# sfx.net
KiCad netlist of a schematic drawn in EAGLE
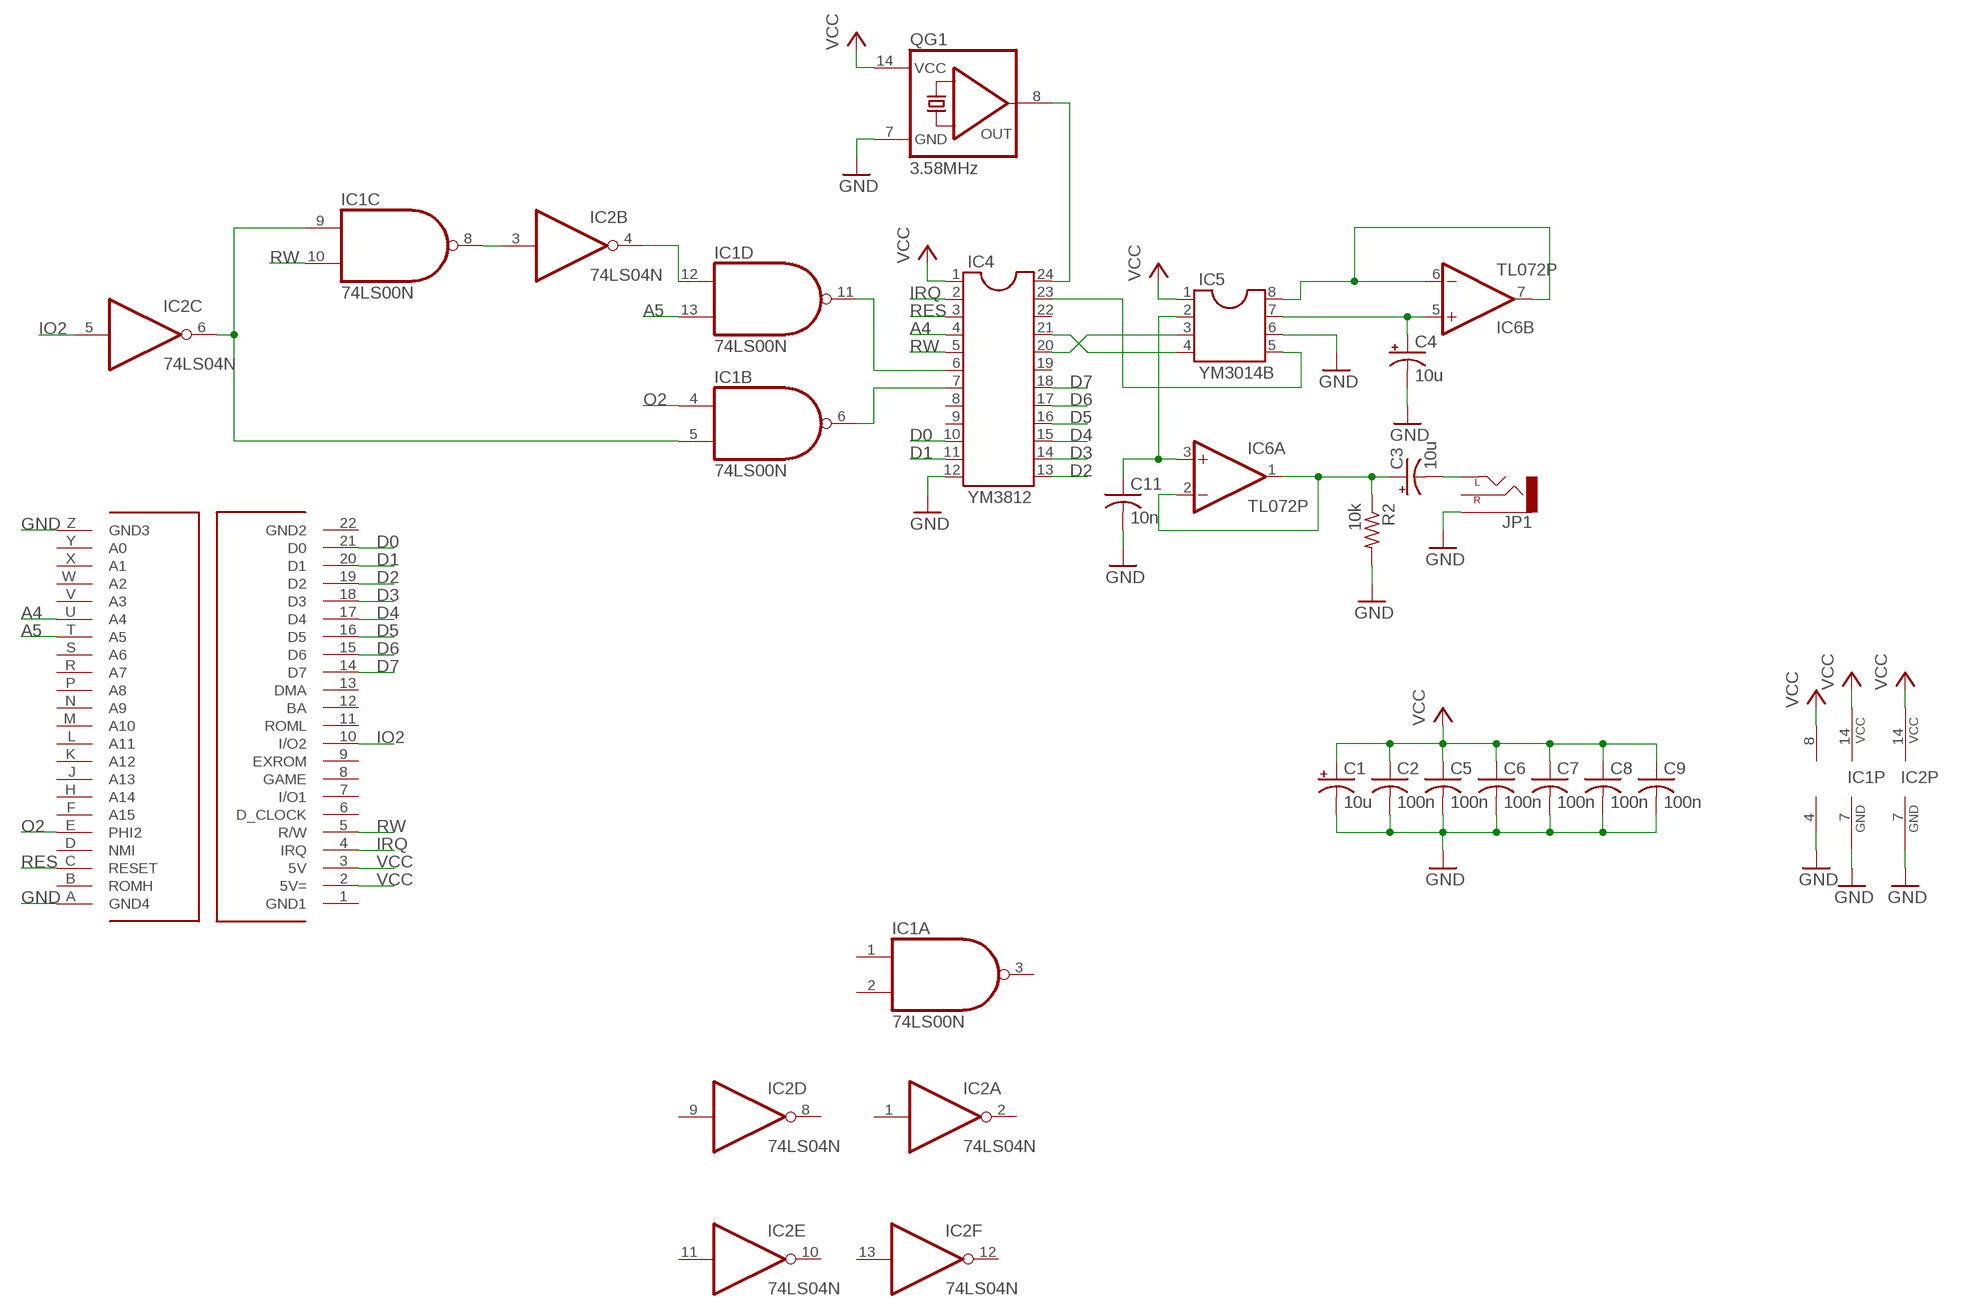
[diagram p0: schematic, sheet 1]

(export (version "E")
  (design (tool "Eeschema 10.0.6"))
  (components
    (comp (ref "C1")
      (value "10u")
      (footprint "eagle-import:E2,5-6")
      (libsource (lib "eagle-import") (part "CPOL-USE2.5-6"))
    )
    (comp (ref "C2")
      (value "100n")
      (footprint "eagle-import:C025-025X050")
      (libsource (lib "eagle-import") (part "C-US025-025X050"))
    )
    (comp (ref "C3")
      (value "10u")
      (footprint "eagle-import:E2,5-6")
      (libsource (lib "eagle-import") (part "CPOL-USE2.5-6"))
    )
    (comp (ref "C4")
      (value "10u")
      (footprint "eagle-import:E2,5-6")
      (libsource (lib "eagle-import") (part "CPOL-USE2.5-6"))
    )
    (comp (ref "C5")
      (value "100n")
      (footprint "eagle-import:C025-025X050")
      (libsource (lib "eagle-import") (part "C-US025-025X050"))
    )
    (comp (ref "C6")
      (value "100n")
      (footprint "eagle-import:C025-025X050")
      (libsource (lib "eagle-import") (part "C-US025-025X050"))
    )
    (comp (ref "C7")
      (value "100n")
      (footprint "eagle-import:C025-025X050")
      (libsource (lib "eagle-import") (part "C-US025-025X050"))
    )
    (comp (ref "C8")
      (value "100n")
      (footprint "eagle-import:C025-025X050")
      (libsource (lib "eagle-import") (part "C-US025-025X050"))
    )
    (comp (ref "C9")
      (value "100n")
      (footprint "eagle-import:C025-025X050")
      (libsource (lib "eagle-import") (part "C-US025-025X050"))
    )
    (comp (ref "C11")
      (value "10n")
      (footprint "eagle-import:C025-025X050")
      (libsource (lib "eagle-import") (part "C-US025-025X050"))
    )
    (comp (ref "IC1")
      (value "74LS00N")
      (footprint "eagle-import:DIL14")
      (libsource (lib "eagle-import") (part "7400NLS"))
    )
    (comp (ref "IC2")
      (value "74LS04N")
      (footprint "eagle-import:DIL14")
      (libsource (lib "eagle-import") (part "7404NLS"))
    )
    (comp (ref "IC4")
      (value "YM3812")
      (footprint "eagle-import:DIL24-6")
      (libsource (lib "eagle-import") (part "DIL24-6"))
    )
    (comp (ref "IC5")
      (value "YM3014B")
      (footprint "eagle-import:DIL08")
      (libsource (lib "eagle-import") (part "DIL8"))
    )
    (comp (ref "IC6")
      (value "TL072P")
      (footprint "eagle-import:DIL08")
      (libsource (lib "eagle-import") (part "TL072P"))
    )
    (comp (ref "JP1")
      (value "AUDIO-JACKPTH")
      (footprint "eagle-import:AUDIO-JACK")
      (libsource (lib "eagle-import") (part "AUDIO-JACKPTH"))
    )
    (comp (ref "QG1")
      (value "3.58MHz")
      (footprint "eagle-import:DIL14S")
      (libsource (lib "eagle-import") (part "QG5860"))
    )
    (comp (ref "R2")
      (value "10k")
      (footprint "eagle-import:0204_7")
      (libsource (lib "eagle-import") (part "R-US_0204/7"))
    )
    (comp (ref "U$1")
      (value "EASYFLASH_1.4.1_REV_B_C64_EXPANSION__CARTRIDGE")
      (footprint "eagle-import:EASYFLASH_1.4.1_REV_B_C64_EXPANSION__CARTRIDGE")
      (libsource (lib "eagle-import") (part "EASYFLASH_1.4.1_REV_B_C64_EXPANSION__CARTRIDGE"))
    )
  )
  (nets
    (net (code "1") (name "/A4") (class "Default")
      (node (ref "IC4") (pin "4") (pinfunction "4_4") (pintype "passive"))
      (node (ref "U$1") (pin "U") (pinfunction "A4_U") (pintype "bidirectional"))
    )
    (net (code "2") (name "/A5") (class "Default")
      (node (ref "IC1") (pin "13") (pinfunction "I1_13") (pintype "input"))
      (node (ref "U$1") (pin "T") (pinfunction "A5_T") (pintype "bidirectional"))
    )
    (net (code "3") (name "/D0") (class "Default")
      (node (ref "IC4") (pin "10") (pinfunction "10_10") (pintype "passive"))
      (node (ref "U$1") (pin "21") (pinfunction "D0_21") (pintype "bidirectional"))
    )
    (net (code "4") (name "/D1") (class "Default")
      (node (ref "IC4") (pin "11") (pinfunction "11_11") (pintype "passive"))
      (node (ref "U$1") (pin "20") (pinfunction "D1_20") (pintype "bidirectional"))
    )
    (net (code "5") (name "/D2") (class "Default")
      (node (ref "IC4") (pin "13") (pinfunction "13_13") (pintype "passive"))
      (node (ref "U$1") (pin "19") (pinfunction "D2_19") (pintype "bidirectional"))
    )
    (net (code "6") (name "/D3") (class "Default")
      (node (ref "IC4") (pin "14") (pinfunction "14_14") (pintype "passive"))
      (node (ref "U$1") (pin "18") (pinfunction "D3_18") (pintype "bidirectional"))
    )
    (net (code "7") (name "/D4") (class "Default")
      (node (ref "IC4") (pin "15") (pinfunction "15_15") (pintype "passive"))
      (node (ref "U$1") (pin "17") (pinfunction "D4_17") (pintype "bidirectional"))
    )
    (net (code "8") (name "/D5") (class "Default")
      (node (ref "IC4") (pin "16") (pinfunction "16_16") (pintype "passive"))
      (node (ref "U$1") (pin "16") (pinfunction "D5_16") (pintype "bidirectional"))
    )
    (net (code "9") (name "/D6") (class "Default")
      (node (ref "IC4") (pin "17") (pinfunction "17_17") (pintype "passive"))
      (node (ref "U$1") (pin "15") (pinfunction "D6_15") (pintype "bidirectional"))
    )
    (net (code "10") (name "/D7") (class "Default")
      (node (ref "IC4") (pin "18") (pinfunction "18_18") (pintype "passive"))
      (node (ref "U$1") (pin "14") (pinfunction "D7_14") (pintype "bidirectional"))
    )
    (net (code "11") (name "/IO2") (class "Default")
      (node (ref "IC2") (pin "5") (pinfunction "I_5") (pintype "input"))
      (node (ref "U$1") (pin "10") (pinfunction "I/O2_10") (pintype "bidirectional"))
    )
    (net (code "12") (name "/IRQ") (class "Default")
      (node (ref "IC4") (pin "2") (pinfunction "2_2") (pintype "passive"))
      (node (ref "U$1") (pin "4") (pinfunction "IRQ_4") (pintype "bidirectional"))
    )
    (net (code "13") (name "/O2") (class "Default")
      (node (ref "IC1") (pin "4") (pinfunction "I0_4") (pintype "input"))
      (node (ref "U$1") (pin "E") (pinfunction "PHI2_E") (pintype "bidirectional"))
    )
    (net (code "14") (name "/RES") (class "Default")
      (node (ref "IC4") (pin "3") (pinfunction "3_3") (pintype "passive"))
      (node (ref "U$1") (pin "C") (pinfunction "RESET_C") (pintype "bidirectional"))
    )
    (net (code "15") (name "/RW") (class "Default")
      (node (ref "IC1") (pin "10") (pinfunction "I1_10") (pintype "input"))
      (node (ref "IC4") (pin "5") (pinfunction "5_5") (pintype "passive"))
      (node (ref "U$1") (pin "5") (pinfunction "R/W_5") (pintype "bidirectional"))
    )
    (net (code "16") (name "GND") (class "Default")
      (node (ref "C1") (pin "-") (pinfunction "-_-") (pintype "passive"))
      (node (ref "C11") (pin "2") (pinfunction "2_2") (pintype "passive"))
      (node (ref "C2") (pin "2") (pinfunction "2_2") (pintype "passive"))
      (node (ref "C4") (pin "-") (pinfunction "-_-") (pintype "passive"))
      (node (ref "C5") (pin "2") (pinfunction "2_2") (pintype "passive"))
      (node (ref "C6") (pin "2") (pinfunction "2_2") (pintype "passive"))
      (node (ref "C7") (pin "2") (pinfunction "2_2") (pintype "passive"))
      (node (ref "C8") (pin "2") (pinfunction "2_2") (pintype "passive"))
      (node (ref "C9") (pin "2") (pinfunction "2_2") (pintype "passive"))
      (node (ref "IC1") (pin "7") (pinfunction "GND_7") (pintype "power_in"))
      (node (ref "IC2") (pin "7") (pinfunction "GND_7") (pintype "power_in"))
      (node (ref "IC4") (pin "12") (pinfunction "12_12") (pintype "passive"))
      (node (ref "IC5") (pin "6") (pinfunction "6_6") (pintype "passive"))
      (node (ref "IC6") (pin "4") (pinfunction "V-_4") (pintype "power_in"))
      (node (ref "JP1") (pin "SLEEVE") (pinfunction "SLEEVE_SLEEVE") (pintype "bidirectional"))
      (node (ref "QG1") (pin "7") (pinfunction "GND_7") (pintype "power_in"))
      (node (ref "R2") (pin "2") (pinfunction "2_2") (pintype "passive"))
      (node (ref "U$1") (pin "A") (pinfunction "GND4_A") (pintype "bidirectional"))
      (node (ref "U$1") (pin "Z") (pinfunction "GND3_Z") (pintype "bidirectional"))
    )
    (net (code "17") (name "Net-(IC1B-I1)") (class "Default")
      (node (ref "IC1") (pin "5") (pinfunction "I1_5") (pintype "input"))
      (node (ref "IC1") (pin "9") (pinfunction "I0_9") (pintype "input"))
      (node (ref "IC2") (pin "6") (pinfunction "O_6") (pintype "output"))
    )
    (net (code "18") (name "Net-(IC1B-O)") (class "Default")
      (node (ref "IC1") (pin "6") (pinfunction "O_6") (pintype "output"))
      (node (ref "IC4") (pin "7") (pinfunction "7_7") (pintype "passive"))
    )
    (net (code "19") (name "Net-(IC1C-O)") (class "Default")
      (node (ref "IC1") (pin "8") (pinfunction "O_8") (pintype "output"))
      (node (ref "IC2") (pin "3") (pinfunction "I_3") (pintype "input"))
    )
    (net (code "20") (name "Net-(IC1D-I0)") (class "Default")
      (node (ref "IC1") (pin "12") (pinfunction "I0_12") (pintype "input"))
      (node (ref "IC2") (pin "4") (pinfunction "O_4") (pintype "output"))
    )
    (net (code "21") (name "Net-(IC1D-O)") (class "Default")
      (node (ref "IC1") (pin "11") (pinfunction "O_11") (pintype "output"))
      (node (ref "IC4") (pin "6") (pinfunction "6_6") (pintype "passive"))
    )
    (net (code "22") (name "Net-(IC4-Pad20)") (class "Default")
      (node (ref "IC4") (pin "20") (pinfunction "20_20") (pintype "passive"))
      (node (ref "IC5") (pin "3") (pinfunction "3_3") (pintype "passive"))
    )
    (net (code "23") (name "Net-(IC4-Pad21)") (class "Default")
      (node (ref "IC4") (pin "21") (pinfunction "21_21") (pintype "passive"))
      (node (ref "IC5") (pin "4") (pinfunction "4_4") (pintype "passive"))
    )
    (net (code "24") (name "Net-(IC4-Pad23)") (class "Default")
      (node (ref "IC4") (pin "23") (pinfunction "23_23") (pintype "passive"))
      (node (ref "IC5") (pin "5") (pinfunction "5_5") (pintype "passive"))
    )
    (net (code "25") (name "Net-(IC6A-+IN)") (class "Default")
      (node (ref "C11") (pin "1") (pinfunction "1_1") (pintype "passive"))
      (node (ref "IC5") (pin "2") (pinfunction "2_2") (pintype "passive"))
      (node (ref "IC6") (pin "3") (pinfunction "+IN_3") (pintype "input"))
    )
    (net (code "26") (name "Net-(IC6A--IN)") (class "Default")
      (node (ref "C3") (pin "+") (pinfunction "+_+") (pintype "passive"))
      (node (ref "IC6") (pin "1") (pinfunction "OUT_1") (pintype "output"))
      (node (ref "IC6") (pin "2") (pinfunction "-IN_2") (pintype "input"))
      (node (ref "R2") (pin "1") (pinfunction "1_1") (pintype "passive"))
    )
    (net (code "27") (name "Net-(IC6B-+IN)") (class "Default")
      (node (ref "C4") (pin "+") (pinfunction "+_+") (pintype "passive"))
      (node (ref "IC5") (pin "7") (pinfunction "7_7") (pintype "passive"))
      (node (ref "IC6") (pin "5") (pinfunction "+IN_5") (pintype "input"))
    )
    (net (code "28") (name "Net-(IC6B--IN)") (class "Default")
      (node (ref "IC5") (pin "8") (pinfunction "8_8") (pintype "passive"))
      (node (ref "IC6") (pin "6") (pinfunction "-IN_6") (pintype "input"))
      (node (ref "IC6") (pin "7") (pinfunction "OUT_7") (pintype "output"))
    )
    (net (code "29") (name "Net-(JP1-LEFT)") (class "Default")
      (node (ref "C3") (pin "-") (pinfunction "-_-") (pintype "passive"))
      (node (ref "JP1") (pin "TIP") (pinfunction "LEFT_TIP") (pintype "bidirectional"))
    )
    (net (code "30") (name "Net-(QG1-OUT)") (class "Default")
      (node (ref "IC4") (pin "24") (pinfunction "24_24") (pintype "passive"))
      (node (ref "QG1") (pin "8") (pinfunction "OUT_8") (pintype "output"))
    )
    (net (code "31") (name "VCC") (class "Default")
      (node (ref "C1") (pin "+") (pinfunction "+_+") (pintype "passive"))
      (node (ref "C2") (pin "1") (pinfunction "1_1") (pintype "passive"))
      (node (ref "C5") (pin "1") (pinfunction "1_1") (pintype "passive"))
      (node (ref "C6") (pin "1") (pinfunction "1_1") (pintype "passive"))
      (node (ref "C7") (pin "1") (pinfunction "1_1") (pintype "passive"))
      (node (ref "C8") (pin "1") (pinfunction "1_1") (pintype "passive"))
      (node (ref "C9") (pin "1") (pinfunction "1_1") (pintype "passive"))
      (node (ref "IC1") (pin "14") (pinfunction "VCC_14") (pintype "power_in"))
      (node (ref "IC2") (pin "14") (pinfunction "VCC_14") (pintype "power_in"))
      (node (ref "IC4") (pin "1") (pinfunction "1_1") (pintype "passive"))
      (node (ref "IC5") (pin "1") (pinfunction "1_1") (pintype "passive"))
      (node (ref "IC6") (pin "8") (pinfunction "V+_8") (pintype "power_in"))
      (node (ref "QG1") (pin "14") (pinfunction "VCC_14") (pintype "power_in"))
      (node (ref "U$1") (pin "2") (pinfunction "5V=_2") (pintype "bidirectional"))
      (node (ref "U$1") (pin "3") (pinfunction "5V_3") (pintype "bidirectional"))
    )
    (net (code "32") (name "unconnected-(IC1A-I0-Pad1)") (class "Default")
      (node (ref "IC1") (pin "1") (pinfunction "I0_1") (pintype "input"))
    )
    (net (code "33") (name "unconnected-(IC1A-I1-Pad2)") (class "Default")
      (node (ref "IC1") (pin "2") (pinfunction "I1_2") (pintype "input"))
    )
    (net (code "34") (name "unconnected-(IC1A-O-Pad3)") (class "Default")
      (node (ref "IC1") (pin "3") (pinfunction "O_3") (pintype "output"))
    )
    (net (code "35") (name "unconnected-(IC2A-I-Pad1)") (class "Default")
      (node (ref "IC2") (pin "1") (pinfunction "I_1") (pintype "input"))
    )
    (net (code "36") (name "unconnected-(IC2A-O-Pad2)") (class "Default")
      (node (ref "IC2") (pin "2") (pinfunction "O_2") (pintype "output"))
    )
    (net (code "37") (name "unconnected-(IC2D-I-Pad9)") (class "Default")
      (node (ref "IC2") (pin "9") (pinfunction "I_9") (pintype "input"))
    )
    (net (code "38") (name "unconnected-(IC2D-O-Pad8)") (class "Default")
      (node (ref "IC2") (pin "8") (pinfunction "O_8") (pintype "output"))
    )
    (net (code "39") (name "unconnected-(IC2E-I-Pad11)") (class "Default")
      (node (ref "IC2") (pin "11") (pinfunction "I_11") (pintype "input"))
    )
    (net (code "40") (name "unconnected-(IC2E-O-Pad10)") (class "Default")
      (node (ref "IC2") (pin "10") (pinfunction "O_10") (pintype "output"))
    )
    (net (code "41") (name "unconnected-(IC2F-I-Pad13)") (class "Default")
      (node (ref "IC2") (pin "13") (pinfunction "I_13") (pintype "input"))
    )
    (net (code "42") (name "unconnected-(IC2F-O-Pad12)") (class "Default")
      (node (ref "IC2") (pin "12") (pinfunction "O_12") (pintype "output"))
    )
    (net (code "43") (name "unconnected-(IC4-Pad8)") (class "Default")
      (node (ref "IC4") (pin "8") (pinfunction "8_8") (pintype "passive"))
    )
    (net (code "44") (name "unconnected-(IC4-Pad9)") (class "Default")
      (node (ref "IC4") (pin "9") (pinfunction "9_9") (pintype "passive"))
    )
    (net (code "45") (name "unconnected-(IC4-Pad19)") (class "Default")
      (node (ref "IC4") (pin "19") (pinfunction "19_19") (pintype "passive"))
    )
    (net (code "46") (name "unconnected-(IC4-Pad22)") (class "Default")
      (node (ref "IC4") (pin "22") (pinfunction "22_22") (pintype "passive"))
    )
    (net (code "47") (name "unconnected-(JP1-RIGHT-PadRING)") (class "Default")
      (node (ref "JP1") (pin "RING") (pinfunction "RIGHT_RING") (pintype "bidirectional"))
    )
    (net (code "48") (name "unconnected-(U$1-A0-PadY)") (class "Default")
      (node (ref "U$1") (pin "Y") (pinfunction "A0_Y") (pintype "bidirectional"))
    )
    (net (code "49") (name "unconnected-(U$1-A1-PadX)") (class "Default")
      (node (ref "U$1") (pin "X") (pinfunction "A1_X") (pintype "bidirectional"))
    )
    (net (code "50") (name "unconnected-(U$1-A2-PadW)") (class "Default")
      (node (ref "U$1") (pin "W") (pinfunction "A2_W") (pintype "bidirectional"))
    )
    (net (code "51") (name "unconnected-(U$1-A3-PadV)") (class "Default")
      (node (ref "U$1") (pin "V") (pinfunction "A3_V") (pintype "bidirectional"))
    )
    (net (code "52") (name "unconnected-(U$1-A6-PadS)") (class "Default")
      (node (ref "U$1") (pin "S") (pinfunction "A6_S") (pintype "bidirectional"))
    )
    (net (code "53") (name "unconnected-(U$1-A7-PadR)") (class "Default")
      (node (ref "U$1") (pin "R") (pinfunction "A7_R") (pintype "bidirectional"))
    )
    (net (code "54") (name "unconnected-(U$1-A8-PadP)") (class "Default")
      (node (ref "U$1") (pin "P") (pinfunction "A8_P") (pintype "bidirectional"))
    )
    (net (code "55") (name "unconnected-(U$1-A9-PadN)") (class "Default")
      (node (ref "U$1") (pin "N") (pinfunction "A9_N") (pintype "bidirectional"))
    )
    (net (code "56") (name "unconnected-(U$1-A10-PadM)") (class "Default")
      (node (ref "U$1") (pin "M") (pinfunction "A10_M") (pintype "bidirectional"))
    )
    (net (code "57") (name "unconnected-(U$1-A11-PadL)") (class "Default")
      (node (ref "U$1") (pin "L") (pinfunction "A11_L") (pintype "bidirectional"))
    )
    (net (code "58") (name "unconnected-(U$1-A12-PadK)") (class "Default")
      (node (ref "U$1") (pin "K") (pinfunction "A12_K") (pintype "bidirectional"))
    )
    (net (code "59") (name "unconnected-(U$1-A13-PadJ)") (class "Default")
      (node (ref "U$1") (pin "J") (pinfunction "A13_J") (pintype "bidirectional"))
    )
    (net (code "60") (name "unconnected-(U$1-A14-PadH)") (class "Default")
      (node (ref "U$1") (pin "H") (pinfunction "A14_H") (pintype "bidirectional"))
    )
    (net (code "61") (name "unconnected-(U$1-A15-PadF)") (class "Default")
      (node (ref "U$1") (pin "F") (pinfunction "A15_F") (pintype "bidirectional"))
    )
    (net (code "62") (name "unconnected-(U$1-BA-Pad12)") (class "Default")
      (node (ref "U$1") (pin "12") (pinfunction "BA_12") (pintype "bidirectional"))
    )
    (net (code "63") (name "unconnected-(U$1-DMA-Pad13)") (class "Default")
      (node (ref "U$1") (pin "13") (pinfunction "DMA_13") (pintype "bidirectional"))
    )
    (net (code "64") (name "unconnected-(U$1-D_CLOCK-Pad6)") (class "Default")
      (node (ref "U$1") (pin "6") (pinfunction "D_CLOCK_6") (pintype "bidirectional"))
    )
    (net (code "65") (name "unconnected-(U$1-EXROM-Pad9)") (class "Default")
      (node (ref "U$1") (pin "9") (pinfunction "EXROM_9") (pintype "bidirectional"))
    )
    (net (code "66") (name "unconnected-(U$1-GAME-Pad8)") (class "Default")
      (node (ref "U$1") (pin "8") (pinfunction "GAME_8") (pintype "bidirectional"))
    )
    (net (code "67") (name "unconnected-(U$1-GND1-Pad1)") (class "Default")
      (node (ref "U$1") (pin "1") (pinfunction "GND1_1") (pintype "bidirectional"))
    )
    (net (code "68") (name "unconnected-(U$1-GND2-Pad22)") (class "Default")
      (node (ref "U$1") (pin "22") (pinfunction "GND2_22") (pintype "bidirectional"))
    )
    (net (code "69") (name "unconnected-(U$1-I{slash}O1-Pad7)") (class "Default")
      (node (ref "U$1") (pin "7") (pinfunction "I/O1_7") (pintype "bidirectional"))
    )
    (net (code "70") (name "unconnected-(U$1-NMI-PadD)") (class "Default")
      (node (ref "U$1") (pin "D") (pinfunction "NMI_D") (pintype "bidirectional"))
    )
    (net (code "71") (name "unconnected-(U$1-ROMH-PadB)") (class "Default")
      (node (ref "U$1") (pin "B") (pinfunction "ROMH_B") (pintype "bidirectional"))
    )
    (net (code "72") (name "unconnected-(U$1-ROML-Pad11)") (class "Default")
      (node (ref "U$1") (pin "11") (pinfunction "ROML_11") (pintype "bidirectional"))
    )
  )
)
